# adaptador2.net
KiCad netlist of a schematic drawn in EAGLE
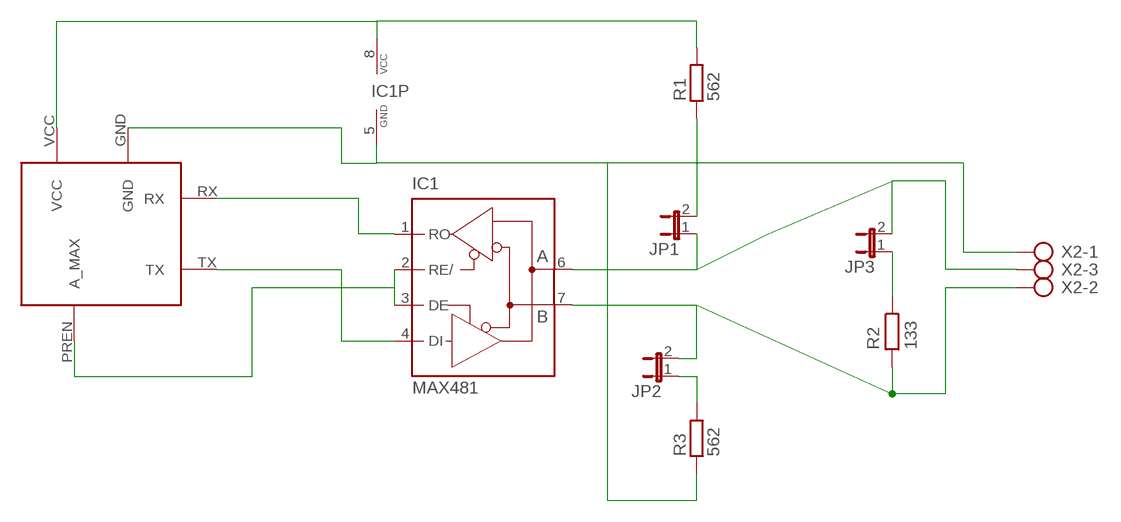
[diagram p0: schematic, sheet 1]

(export (version "E")
  (design (tool "Eeschema 10.0.6"))
  (components
    (comp (ref "1")
      (value "MOD_ADAPTADOR")
      (footprint "eagle-import:ADAPTADOR")
      (libsource (lib "eagle-import") (part "MOD_ADAPTADOR"))
    )
    (comp (ref "IC1")
      (value "MAX481")
      (footprint "eagle-import:DIL08")
      (fields (field (name "MPN") "MAX481CPA+"))
      (libsource (lib "eagle-import") (part "MAX481CPA"))
    )
    (comp (ref "JP1")
      (value "JP1E")
      (footprint "eagle-import:JP1")
      (libsource (lib "eagle-import") (part "JP1E"))
    )
    (comp (ref "JP2")
      (value "JP1E")
      (footprint "eagle-import:JP1")
      (libsource (lib "eagle-import") (part "JP1E"))
    )
    (comp (ref "JP3")
      (value "JP1E")
      (footprint "eagle-import:JP1")
      (libsource (lib "eagle-import") (part "JP1E"))
    )
    (comp (ref "R1")
      (value "562")
      (footprint "eagle-import:0207_10")
      (libsource (lib "eagle-import") (part "R-EU_0207/10"))
    )
    (comp (ref "R2")
      (value "133")
      (footprint "eagle-import:0207_10")
      (libsource (lib "eagle-import") (part "R-EU_0207/10"))
    )
    (comp (ref "R3")
      (value "562")
      (footprint "eagle-import:0207_10")
      (libsource (lib "eagle-import") (part "R-EU_0207/10"))
    )
    (comp (ref "X2")
      (value "AK300/3")
      (footprint "eagle-import:AK300_3")
      (libsource (lib "eagle-import") (part "AK300/3"))
    )
  )
  (nets
    (net (code "1") (name "Net-(1-A_MAX)") (class "Default")
      (node (ref "1") (pin "PREN") (pinfunction "A_MAX_PREN") (pintype "output"))
      (node (ref "IC1") (pin "2") (pinfunction "RE/_2") (pintype "input"))
      (node (ref "IC1") (pin "3") (pinfunction "DE_3") (pintype "input"))
    )
    (net (code "2") (name "Net-(IC1A-A)") (class "Default")
      (node (ref "IC1") (pin "6") (pinfunction "A_6") (pintype "passive"))
      (node (ref "JP1") (pin "1") (pinfunction "1_1") (pintype "passive"))
      (node (ref "JP3") (pin "2") (pinfunction "2_2") (pintype "passive"))
      (node (ref "X2") (pin "3") (pinfunction "KL_3") (pintype "passive"))
    )
    (net (code "3") (name "Net-(IC1A-B)") (class "Default")
      (node (ref "IC1") (pin "7") (pinfunction "B_7") (pintype "passive"))
      (node (ref "JP2") (pin "2") (pinfunction "2_2") (pintype "passive"))
      (node (ref "R2") (pin "2") (pinfunction "2_2") (pintype "passive"))
      (node (ref "X2") (pin "2") (pinfunction "KL_2") (pintype "passive"))
    )
    (net (code "4") (name "Net-(IC1A-DI)") (class "Default")
      (node (ref "1") (pin "TX") (pinfunction "TX_TX") (pintype "output"))
      (node (ref "IC1") (pin "4") (pinfunction "DI_4") (pintype "input"))
    )
    (net (code "5") (name "Net-(IC1A-RO)") (class "Default")
      (node (ref "1") (pin "RX") (pinfunction "RX_RX") (pintype "input"))
      (node (ref "IC1") (pin "1") (pinfunction "RO_1") (pintype "output"))
    )
    (net (code "6") (name "Net-(IC1B-GND)") (class "Default")
      (node (ref "1") (pin "GND") (pinfunction "GND_GND") (pintype "power_in"))
      (node (ref "IC1") (pin "5") (pinfunction "GND_5") (pintype "power_in"))
      (node (ref "R3") (pin "1") (pinfunction "1_1") (pintype "passive"))
      (node (ref "X2") (pin "1") (pinfunction "KL_1") (pintype "passive"))
    )
    (net (code "7") (name "Net-(IC1B-VCC)") (class "Default")
      (node (ref "1") (pin "VCC") (pinfunction "VCC_VCC") (pintype "power_in"))
      (node (ref "IC1") (pin "8") (pinfunction "VCC_8") (pintype "power_in"))
      (node (ref "R1") (pin "2") (pinfunction "2_2") (pintype "passive"))
    )
    (net (code "8") (name "Net-(JP1-Pad2)") (class "Default")
      (node (ref "JP1") (pin "2") (pinfunction "2_2") (pintype "passive"))
      (node (ref "R1") (pin "1") (pinfunction "1_1") (pintype "passive"))
    )
    (net (code "9") (name "Net-(JP2-Pad1)") (class "Default")
      (node (ref "JP2") (pin "1") (pinfunction "1_1") (pintype "passive"))
      (node (ref "R3") (pin "2") (pinfunction "2_2") (pintype "passive"))
    )
    (net (code "10") (name "Net-(JP3-Pad1)") (class "Default")
      (node (ref "JP3") (pin "1") (pinfunction "1_1") (pintype "passive"))
      (node (ref "R2") (pin "1") (pinfunction "1_1") (pintype "passive"))
    )
  )
)
